# SD.net
KiCad netlist of a schematic drawn in Altium Designer
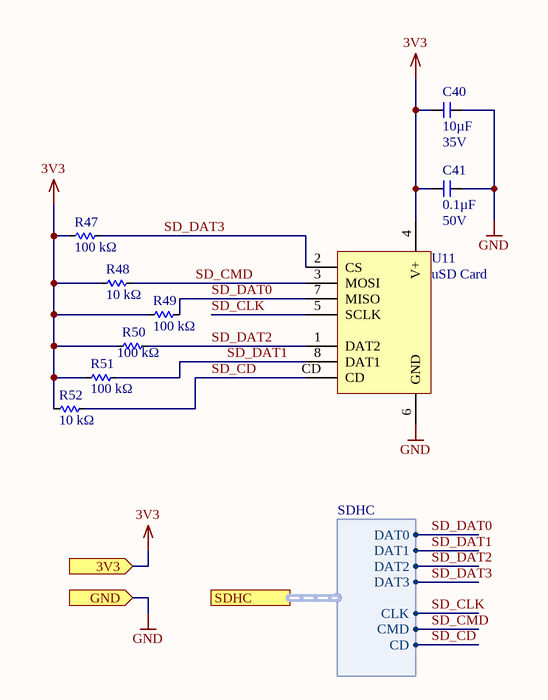
[diagram p0: SD.SchDoc]

(export (version "E")
  (design (tool "Eeschema 10.0.6"))
  (components
    (comp (ref "C40")
      (value "__template_cap")
      (footprint "C0603")
      (fields
        (field (name "CAPACITANCE (SHORTHAND)") "10µF")
        (field (name "RATED VOLTAGE") "35V")
        (field (name "MANUFACTURER") "Murata Electronics North America")
      )
      (libsource (lib "passives") (part "__template_cap"))
    )
    (comp (ref "C41")
      (value "__template_cap")
      (footprint "C0603")
      (fields
        (field (name "CAPACITANCE (SHORTHAND)") "0.1µF")
        (field (name "RATED VOLTAGE") "50V")
        (field (name "MANUFACTURER") "Murata Electronics North America")
      )
      (libsource (lib "passives") (part "__template_cap"))
    )
    (comp (ref "R47")
      (value "__template_resistor")
      (footprint "R0603")
      (fields
        (field (name "RESISTANCE") "100 kΩ")
        (field (name "MANUFACTURER PART NUMBER") "RC0603FR-07100KL")
        (field (name "MANUFACTURER") "Yageo")
        (field (name "TOLERANCE") "±1%")
      )
      (libsource (lib "passives") (part "__template_resistor"))
    )
    (comp (ref "R48")
      (value "__template_resistor")
      (footprint "R0603")
      (fields
        (field (name "RESISTANCE") "10 kΩ")
        (field (name "MANUFACTURER PART NUMBER") "RC0603FR-0710KL")
        (field (name "MANUFACTURER") "Yageo")
        (field (name "TOLERANCE") "±1%")
      )
      (libsource (lib "passives") (part "__template_resistor"))
    )
    (comp (ref "R49")
      (value "__template_resistor")
      (footprint "R0603")
      (fields
        (field (name "RESISTANCE") "100 kΩ")
        (field (name "MANUFACTURER PART NUMBER") "RC0603FR-07100KL")
        (field (name "MANUFACTURER") "Yageo")
        (field (name "TOLERANCE") "±1%")
      )
      (libsource (lib "passives") (part "__template_resistor"))
    )
    (comp (ref "R50")
      (value "__template_resistor")
      (footprint "R0603")
      (fields
        (field (name "RESISTANCE") "100 kΩ")
        (field (name "MANUFACTURER PART NUMBER") "RC0603FR-07100KL")
        (field (name "MANUFACTURER") "Yageo")
        (field (name "TOLERANCE") "±1%")
      )
      (libsource (lib "passives") (part "__template_resistor"))
    )
    (comp (ref "R51")
      (value "__template_resistor")
      (footprint "R0603")
      (fields
        (field (name "RESISTANCE") "100 kΩ")
        (field (name "MANUFACTURER PART NUMBER") "RC0603FR-07100KL")
        (field (name "MANUFACTURER") "Yageo")
        (field (name "TOLERANCE") "±1%")
      )
      (libsource (lib "passives") (part "__template_resistor"))
    )
    (comp (ref "R52")
      (value "__template_resistor")
      (footprint "R0603")
      (fields
        (field (name "RESISTANCE") "10 kΩ")
        (field (name "MANUFACTURER PART NUMBER") "RC0603FR-0710KL")
        (field (name "MANUFACTURER") "Yageo")
        (field (name "TOLERANCE") "±1%")
      )
      (libsource (lib "passives") (part "__template_resistor"))
    )
    (comp (ref "U11")
      (value "uSD Card")
      (footprint "MICROSD_CARD_SOCKET")
      (description "MICROSD CARD HOLDER, PUSH-PUSH")
      (fields (field (name "MANUFACTURER") "3M") (field (name "MANUFACTURER PART NUMBER") "2908-05WB-MG"))
      (libsource (lib "SSI") (part "MICRO_SD_CARD_HOLDER"))
    )
  )
  (nets
    (net (code "2") (name "/SD_CD") (class "Default")
      (node (ref "R52") (pin "2") (pintype "passive"))
      (node (ref "U11") (pin "CD") (pinfunction "CD_CD") (pintype "passive"))
    )
    (net (code "3") (name "/SD_CLK") (class "Default")
      (node (ref "U11") (pin "5") (pinfunction "SCLK_5") (pintype "passive"))
    )
    (net (code "4") (name "/SD_CMD") (class "Default")
      (node (ref "R48") (pin "2") (pintype "passive"))
      (node (ref "U11") (pin "3") (pinfunction "MOSI_3") (pintype "passive"))
    )
    (net (code "5") (name "/SD_DAT0") (class "Default")
      (node (ref "R49") (pin "2") (pintype "passive"))
      (node (ref "U11") (pin "7") (pinfunction "MISO_7") (pintype "passive"))
    )
    (net (code "6") (name "/SD_DAT1") (class "Default")
      (node (ref "R51") (pin "2") (pintype "passive"))
      (node (ref "U11") (pin "8") (pinfunction "DAT1_8") (pintype "passive"))
    )
    (net (code "7") (name "/SD_DAT2") (class "Default")
      (node (ref "R50") (pin "2") (pintype "passive"))
      (node (ref "U11") (pin "1") (pinfunction "DAT2_1") (pintype "passive"))
    )
    (net (code "8") (name "/SD_DAT3") (class "Default")
      (node (ref "R47") (pin "2") (pintype "passive"))
      (node (ref "U11") (pin "2") (pinfunction "CS_2") (pintype "passive"))
    )
    (net (code "10") (name "3V3") (class "Default")
      (node (ref "C40") (pin "2") (pintype "passive"))
      (node (ref "C41") (pin "1") (pintype "passive"))
      (node (ref "R47") (pin "1") (pintype "passive"))
      (node (ref "R48") (pin "1") (pintype "passive"))
      (node (ref "R49") (pin "1") (pintype "passive"))
      (node (ref "R50") (pin "1") (pintype "passive"))
      (node (ref "R51") (pin "1") (pintype "passive"))
      (node (ref "R52") (pin "1") (pintype "passive"))
      (node (ref "U11") (pin "4") (pinfunction "V+_4") (pintype "passive"))
    )
    (net (code "11") (name "GND") (class "Default")
      (node (ref "C40") (pin "1") (pintype "passive"))
      (node (ref "C41") (pin "2") (pintype "passive"))
      (node (ref "U11") (pin "6") (pinfunction "GND_6") (pintype "passive"))
    )
  )
)
